# MCU.net
KiCad netlist of a schematic drawn in Altium Designer
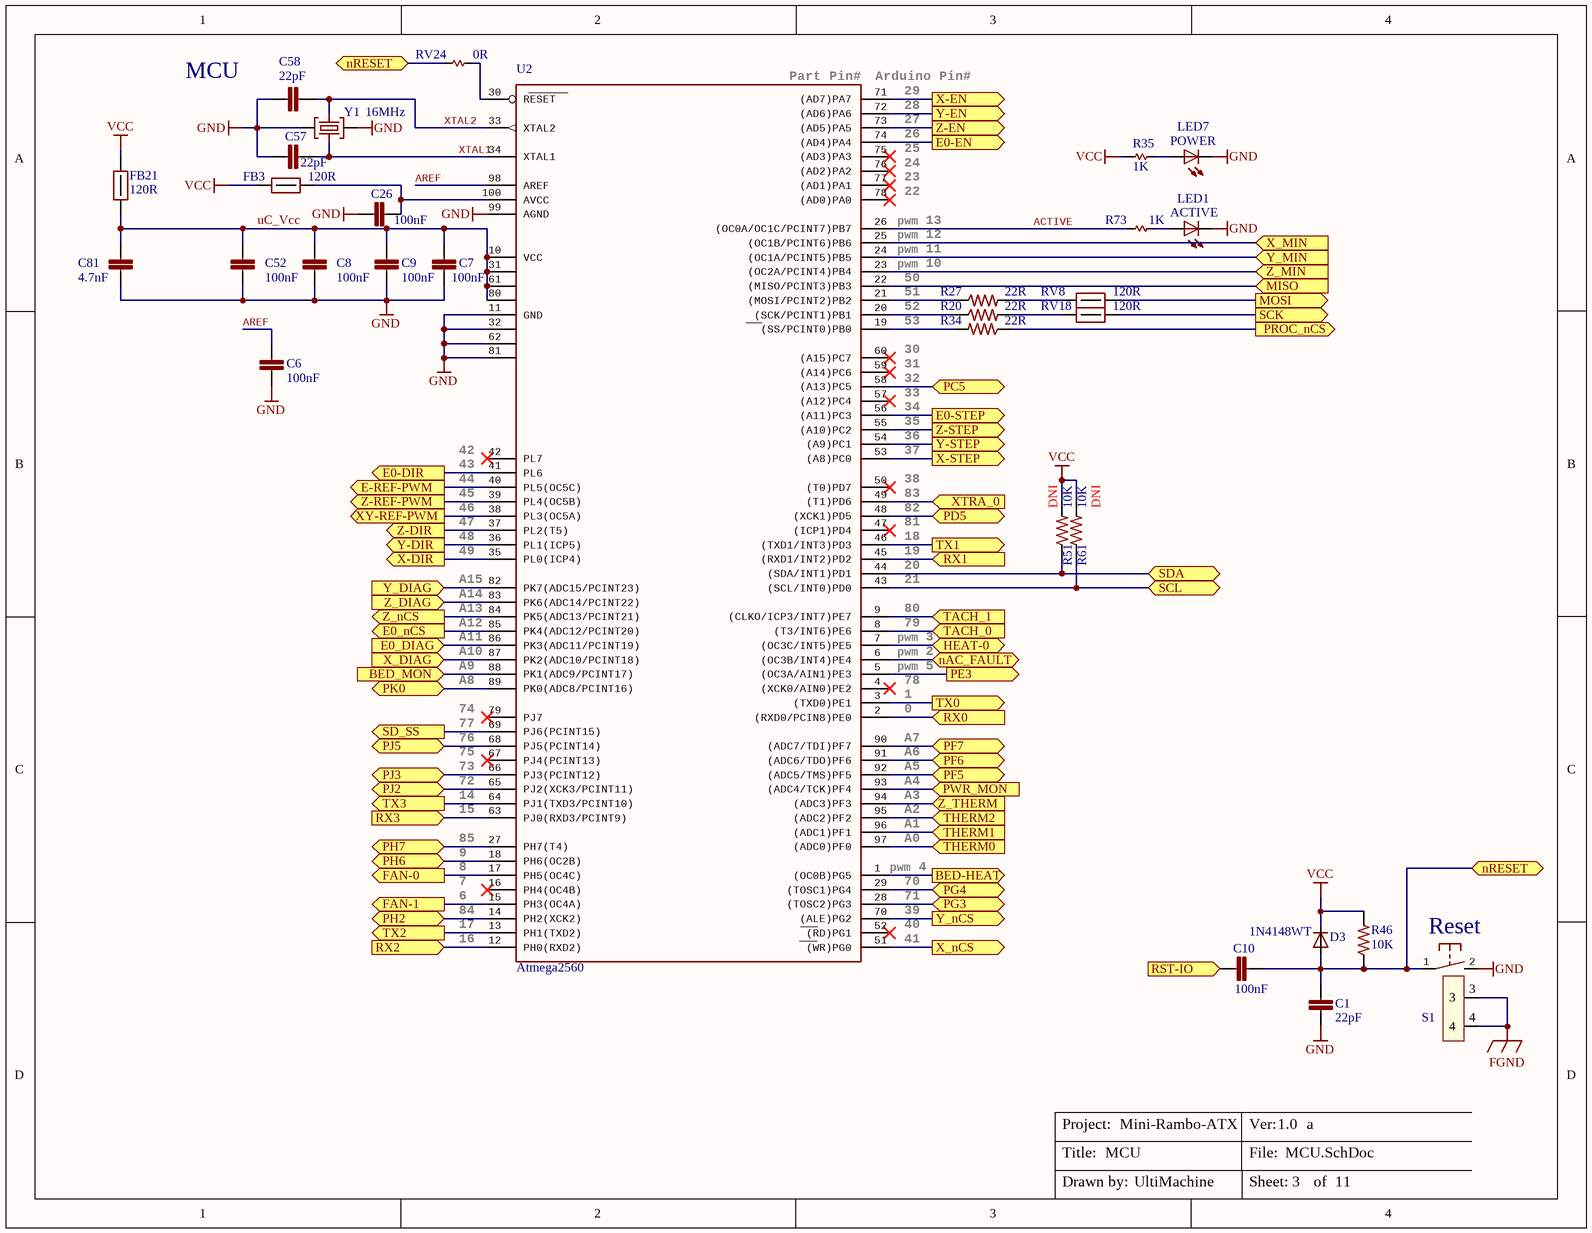
[diagram p0: MCU.SchDoc]

(export (version "E")
  (design (tool "Eeschema 10.0.6"))
  (components
    (comp (ref "C1")
      (value "22pF")
      (footprint "C0402")
      (description "CAP CER 0402 22pF 50V 5% C0G")
      (fields (field (name "MANUFACTURER") "AVX") (field (name "PART") "22pF 50V"))
      (libsource (lib "") (part "04025A220JAT2A_1"))
    )
    (comp (ref "C6")
      (value "100nF")
      (footprint "C0402")
      (description "CAP CER 0402 100nF 16V 10% X7R")
      (fields (field (name "MANUFACTURER") "Murata") (field (name "TOLERANCE") "+/- 10%"))
      (libsource (lib "3Delight") (part "GRM155R71C104KA88D"))
    )
    (comp (ref "C7")
      (value "100nF")
      (footprint "C0402")
      (description "CAP CER 0402 100nF 16V 10% X7R")
      (fields (field (name "MANUFACTURER") "Murata") (field (name "TOLERANCE") "+/- 10%"))
      (libsource (lib "3Delight") (part "GRM155R71C104KA88D"))
    )
    (comp (ref "C8")
      (value "100nF")
      (footprint "C0402")
      (description "CAP CER 0402 100nF 16V 10% X7R")
      (fields (field (name "MANUFACTURER") "Murata") (field (name "TOLERANCE") "+/- 10%"))
      (libsource (lib "3Delight") (part "GRM155R71C104KA88D"))
    )
    (comp (ref "C9")
      (value "100nF")
      (footprint "C0402")
      (description "CAP CER 0402 100nF 16V 10% X7R")
      (fields (field (name "MANUFACTURER") "Murata") (field (name "TOLERANCE") "+/- 10%"))
      (libsource (lib "3Delight") (part "GRM155R71C104KA88D"))
    )
    (comp (ref "C10")
      (value "100nF")
      (footprint "C0402")
      (description "CAP CER 0402 100nF 16V 10% X7R")
      (fields (field (name "MANUFACTURER") "Murata") (field (name "TOLERANCE") "+/- 10%"))
      (libsource (lib "") (part "GRM155R71C104KA88D_2"))
    )
    (comp (ref "C26")
      (value "100nF")
      (footprint "C0402")
      (description "CAP CER 0402 100nF 16V 10% X7R")
      (fields (field (name "MANUFACTURER") "Murata") (field (name "TOLERANCE") "+/- 10%"))
      (libsource (lib "") (part "GRM155R71C104KA88D_1"))
    )
    (comp (ref "C52")
      (value "100nF")
      (footprint "C0402")
      (description "CAP CER 0402 100nF 16V 10% X7R")
      (fields (field (name "MANUFACTURER") "Murata") (field (name "TOLERANCE") "+/- 10%"))
      (libsource (lib "3Delight") (part "GRM155R71C104KA88D"))
    )
    (comp (ref "C57")
      (value "22pF")
      (footprint "C0402")
      (description "CAP CER 0402 22pF 50V 5% C0G")
      (fields (field (name "MANUFACTURER") "AVX") (field (name "PART") "22pF 50V"))
      (libsource (lib "3Delight") (part "04025A220JAT2A"))
    )
    (comp (ref "C58")
      (value "22pF")
      (footprint "C0402")
      (description "CAP CER 0402 22pF 50V 5% C0G")
      (fields (field (name "MANUFACTURER") "AVX") (field (name "PART") "22pF 50V"))
      (libsource (lib "3Delight") (part "04025A220JAT2A"))
    )
    (comp (ref "C81")
      (value "4.7nF")
      (footprint "C0402")
      (description "CAP CER 0402 4.7nF 25V 10% X7R")
      (fields (field (name "MANUFACTURER") "YAGEO") (field (name "TOLERANCE") "+/- 10%"))
      (libsource (lib "3Delight") (part "CC0402KRX7R8BB472"))
    )
    (comp (ref "D3")
      (value "1N4148WT")
      (footprint "SOD523")
      (description "DIODE SOD523")
      (fields (field (name "MANUFACTURER") "Fairchild") (field (name "TOLERANCE") "NA"))
      (libsource (lib "3Delight") (part "1N4148WT"))
    )
    (comp (ref "FB3")
      (value "120R")
      (footprint "FB0603")
      (description "FERRITE BEAD 120 OHM 0603 1LN")
      (fields (field (name "MANUFACTURER") "Samsung") (field (name "PART") "FERRITE 120R 3A 0603"))
      (libsource (lib "3Delight") (part "FERRITE 220R 2.5A 0603"))
    )
    (comp (ref "FB21")
      (value "120R")
      (footprint "FB0603")
      (description "FERRITE BEAD 120 OHM 0603 1LN")
      (fields (field (name "MANUFACTURER") "Samsung") (field (name "PART") "FERRITE 120R 3A 0603"))
      (libsource (lib "Inductors") (part "FERRITE 120R 3A 0603"))
    )
    (comp (ref "LED1")
      (value "YEL")
      (footprint "LED2012120")
      (description "LED 0805 Yellow")
      (fields (field (name "MANUFACTURER") "Dialight") (field (name "TOLERANCE") "NA"))
      (libsource (lib "3Delight") (part "5988140107F"))
    )
    (comp (ref "LED7")
      (value "GRN")
      (footprint "LED2012120")
      (description "LED 0805 Green")
      (fields (field (name "MANUFACTURER") "Dialight") (field (name "TOLERANCE") "NA"))
      (libsource (lib "3Delight") (part "5988170107F"))
    )
    (comp (ref "R20")
      (value "22R")
      (footprint "R0402")
      (description "RES 0402 22r 62.5mW 1%")
      (fields (field (name "MANUFACTURER") "Yageo") (field (name "TOLERANCE") "+/- 1%"))
      (libsource (lib "3Delight") (part "RC0402FR-0722RL"))
    )
    (comp (ref "R27")
      (value "22R")
      (footprint "R0402")
      (description "RES 0402 22r 62.5mW 1%")
      (fields (field (name "MANUFACTURER") "Yageo") (field (name "TOLERANCE") "+/- 1%"))
      (libsource (lib "3Delight") (part "RC0402FR-0722RL"))
    )
    (comp (ref "R34")
      (value "22R")
      (footprint "R0402")
      (description "RES 0402 22r 62.5mW 1%")
      (fields (field (name "MANUFACTURER") "Yageo") (field (name "TOLERANCE") "+/- 1%"))
      (libsource (lib "3Delight") (part "RC0402FR-0722RL"))
    )
    (comp (ref "R35")
      (value "1K")
      (footprint "R0402")
      (description "RES SMD 1K OHM 1% 1/16W 0402")
      (fields (field (name "MANUFACTURER") "Yageo") (field (name "PART") "1k"))
      (libsource (lib "3Delight") (part "RC0402FR-071KL"))
    )
    (comp (ref "R46")
      (value "10K")
      (footprint "R0402")
      (description "RES SMD 10K OHM 1% 1/16W 0402")
      (fields (field (name "MANUFACTURER") "Yageo") (field (name "PART") "10k 1% 0402"))
      (libsource (lib "3Delight") (part "RC0402FR-0710KP"))
    )
    (comp (ref "R51")
      (value "10K")
      (footprint "R0402")
      (description "RES SMD 10K OHM 1% 1/16W 0402")
      (fields
        (field (name "MANUFACTURER") "Yageo")
        (field (name "PART") "10k 1% 0402")
        (field (name "DNI") "DNI")
      )
      (libsource (lib "3Delight") (part "RC0402FR-0710KP"))
    )
    (comp (ref "R61")
      (value "10K")
      (footprint "R0402")
      (description "RES SMD 10K OHM 1% 1/16W 0402")
      (fields
        (field (name "MANUFACTURER") "Yageo")
        (field (name "PART") "10k 1% 0402")
        (field (name "DNI") "DNI")
      )
      (libsource (lib "3Delight") (part "RC0402FR-0710KP"))
    )
    (comp (ref "R73")
      (value "1K")
      (footprint "R0402")
      (description "RES SMD 1K OHM 1% 1/16W 0402")
      (fields (field (name "MANUFACTURER") "Yageo") (field (name "PART") "1k"))
      (libsource (lib "3Delight") (part "RC0402FR-071KL"))
    )
    (comp (ref "RV8")
      (value "120R")
      (footprint "R0402")
      (description "FERRITE BEAD 120 OHM 0402 1LN")
      (fields (field (name "MANUFACTURER") "Taiyo Yuden") (field (name "PART") "FERRITE 120R 1A 0402"))
      (libsource (lib "Inductors") (part "FERRITE 120R 1A 0402"))
    )
    (comp (ref "RV18")
      (value "120R")
      (footprint "R0402")
      (description "FERRITE BEAD 120 OHM 0402 1LN")
      (fields (field (name "MANUFACTURER") "Taiyo Yuden") (field (name "PART") "FERRITE 120R 1A 0402"))
      (libsource (lib "Inductors") (part "FERRITE 120R 1A 0402"))
    )
    (comp (ref "RV24")
      (value "0R")
      (footprint "R0402")
      (description "RES SMD 0.0OHM JUMPER 1/10W 0402")
      (fields (field (name "MANUFACTURER") "Panasonic") (field (name "TOLERANCE") "1%"))
      (libsource (lib "Resistors") (part "0R 0402"))
    )
    (comp (ref "S1")
      (value "1571610-2")
      (footprint "B3F-31XX")
      (description "SWTCH Momentary Washable")
      (fields (field (name "MANUFACTURER") "TE") (field (name "PART") "Tact PB R/A"))
      (libsource (lib "3Delight") (part "1571610-2"))
    )
    (comp (ref "U2")
      (value "Atmega2560")
      (footprint "TSQFP50P1600X1600X120-100L")
      (fields
        (field (name "MANUFACTURER") "Microchip")
        (field (name "PART") "ATMEGA2560")
        (field (name "TOLERANCE") "NA")
      )
      (libsource (lib "ICs-uC") (part "ATMEGA2560AU_SM"))
    )
    (comp (ref "Y1")
      (value "16MHz")
      (footprint "CRYS320250")
      (description "Crystal 16mHz 10ppm 10pF")
      (fields (field (name "MANUFACTURER") "TXC") (field (name "TOLERANCE") "10ppm"))
      (libsource (lib "3Delight") (part "7M-16.000MEEQ-T"))
    )
  )
  (nets
    (net (code "1") (name "/ACTIVE") (class "Default")
      (node (ref "R73") (pin "2") (pinfunction "2_2") (pintype "passive"))
      (node (ref "U2") (pin "26") (pinfunction "(OC0A/OC1C/PCINT7)PB7_26") (pintype "passive"))
    )
    (net (code "2") (name "/AREF") (class "Default")
      (node (ref "C6") (pin "1") (pinfunction "1_1") (pintype "passive"))
      (node (ref "U2") (pin "98") (pinfunction "AREF_98") (pintype "passive"))
    )
    (net (code "3") (name "/BED-HEAT") (class "Default")
      (node (ref "U2") (pin "1") (pinfunction "(OC0B)PG5_1") (pintype "passive"))
    )
    (net (code "4") (name "/BED_MON") (class "Default")
      (node (ref "U2") (pin "88") (pinfunction "PK1(ADC9/PCINT17)_88") (pintype "passive"))
    )
    (net (code "5") (name "/E-REF-PWM") (class "Default")
      (node (ref "U2") (pin "40") (pinfunction "PL5(OC5C)_40") (pintype "passive"))
    )
    (net (code "6") (name "/E0-DIR") (class "Default")
      (node (ref "U2") (pin "41") (pinfunction "PL6_41") (pintype "passive"))
    )
    (net (code "7") (name "/E0-EN") (class "Default")
      (node (ref "U2") (pin "74") (pinfunction "(AD4)PA4_74") (pintype "passive"))
    )
    (net (code "8") (name "/E0-STEP") (class "Default")
      (node (ref "U2") (pin "56") (pinfunction "(A11)PC3_56") (pintype "passive"))
    )
    (net (code "9") (name "/E0_DIAG") (class "Default")
      (node (ref "U2") (pin "86") (pinfunction "PK3(ADC11/PCINT19)_86") (pintype "passive"))
    )
    (net (code "10") (name "/E0_nCS") (class "Default")
      (node (ref "U2") (pin "85") (pinfunction "PK4(ADC12/PCINT20)_85") (pintype "passive"))
    )
    (net (code "11") (name "/FAN-0") (class "Default")
      (node (ref "U2") (pin "17") (pinfunction "PH5(OC4C)_17") (pintype "passive"))
    )
    (net (code "12") (name "/FAN-1") (class "Default")
      (node (ref "U2") (pin "15") (pinfunction "PH3(OC4A)_15") (pintype "passive"))
    )
    (net (code "13") (name "/HEAT-0") (class "Default")
      (node (ref "U2") (pin "7") (pinfunction "(OC3C/INT5)PE5_7") (pintype "passive"))
    )
    (net (code "14") (name "/MISO") (class "Default")
      (node (ref "U2") (pin "22") (pinfunction "(MISO/PCINT3)PB3_22") (pintype "passive"))
    )
    (net (code "15") (name "/MOSI") (class "Default")
      (node (ref "RV8") (pin "2") (pinfunction "2_2") (pintype "passive"))
    )
    (net (code "16") (name "/PC5") (class "Default")
      (node (ref "U2") (pin "58") (pinfunction "(A13)PC5_58") (pintype "passive"))
    )
    (net (code "17") (name "/PD5") (class "Default")
      (node (ref "U2") (pin "48") (pinfunction "(XCK1)PD5_48") (pintype "passive"))
    )
    (net (code "18") (name "/PE3") (class "Default")
      (node (ref "U2") (pin "5") (pinfunction "(OC3A/AIN1)PE3_5") (pintype "passive"))
    )
    (net (code "19") (name "/PF5") (class "Default")
      (node (ref "U2") (pin "92") (pinfunction "(ADC5/TMS)PF5_92") (pintype "passive"))
    )
    (net (code "20") (name "/PF6") (class "Default")
      (node (ref "U2") (pin "91") (pinfunction "(ADC6/TDO)PF6_91") (pintype "passive"))
    )
    (net (code "21") (name "/PF7") (class "Default")
      (node (ref "U2") (pin "90") (pinfunction "(ADC7/TDI)PF7_90") (pintype "passive"))
    )
    (net (code "22") (name "/PG3") (class "Default")
      (node (ref "U2") (pin "28") (pinfunction "(TOSC2)PG3_28") (pintype "passive"))
    )
    (net (code "23") (name "/PG4") (class "Default")
      (node (ref "U2") (pin "29") (pinfunction "(TOSC1)PG4_29") (pintype "passive"))
    )
    (net (code "24") (name "/PH2") (class "Default")
      (node (ref "U2") (pin "14") (pinfunction "PH2(XCK2)_14") (pintype "passive"))
    )
    (net (code "25") (name "/PH6") (class "Default")
      (node (ref "U2") (pin "18") (pinfunction "PH6(OC2B)_18") (pintype "passive"))
    )
    (net (code "26") (name "/PH7") (class "Default")
      (node (ref "U2") (pin "27") (pinfunction "PH7(T4)_27") (pintype "passive"))
    )
    (net (code "27") (name "/PJ2") (class "Default")
      (node (ref "U2") (pin "65") (pinfunction "PJ2(XCK3/PCINT11)_65") (pintype "passive"))
    )
    (net (code "28") (name "/PJ3") (class "Default")
      (node (ref "U2") (pin "66") (pinfunction "PJ3(PCINT12)_66") (pintype "passive"))
    )
    (net (code "29") (name "/PJ5") (class "Default")
      (node (ref "U2") (pin "68") (pinfunction "PJ5(PCINT14)_68") (pintype "passive"))
    )
    (net (code "30") (name "/PK0") (class "Default")
      (node (ref "U2") (pin "89") (pinfunction "PK0(ADC8/PCINT16)_89") (pintype "passive"))
    )
    (net (code "31") (name "/PROC_nCS") (class "Default")
      (node (ref "R34") (pin "1") (pinfunction "1_1") (pintype "passive"))
    )
    (net (code "32") (name "/PWR_MON") (class "Default")
      (node (ref "U2") (pin "93") (pinfunction "(ADC4/TCK)PF4_93") (pintype "passive"))
    )
    (net (code "33") (name "/RST-IO") (class "Default")
      (node (ref "C10") (pin "1") (pinfunction "1_1") (pintype "passive"))
    )
    (net (code "34") (name "/RX0") (class "Default")
      (node (ref "U2") (pin "2") (pinfunction "(RXD0/PCIN8)PE0_2") (pintype "passive"))
    )
    (net (code "35") (name "/RX1") (class "Default")
      (node (ref "U2") (pin "45") (pinfunction "(RXD1/INT2)PD2_45") (pintype "passive"))
    )
    (net (code "36") (name "/RX2") (class "Default")
      (node (ref "U2") (pin "12") (pinfunction "PH0(RXD2)_12") (pintype "passive"))
    )
    (net (code "37") (name "/RX3") (class "Default")
      (node (ref "U2") (pin "63") (pinfunction "PJ0(RXD3/PCINT9)_63") (pintype "passive"))
    )
    (net (code "38") (name "/SCK") (class "Default")
      (node (ref "RV18") (pin "2") (pinfunction "2_2") (pintype "passive"))
    )
    (net (code "39") (name "/SCL") (class "Default")
      (node (ref "R61") (pin "1") (pinfunction "1_1") (pintype "passive"))
      (node (ref "U2") (pin "43") (pinfunction "(SCL/INT0)PD0_43") (pintype "passive"))
    )
    (net (code "40") (name "/SDA") (class "Default")
      (node (ref "R51") (pin "1") (pinfunction "1_1") (pintype "passive"))
      (node (ref "U2") (pin "44") (pinfunction "(SDA/INT1)PD1_44") (pintype "passive"))
    )
    (net (code "41") (name "/SD_SS") (class "Default")
      (node (ref "U2") (pin "69") (pinfunction "PJ6(PCINT15)_69") (pintype "passive"))
    )
    (net (code "42") (name "/TACH_0") (class "Default")
      (node (ref "U2") (pin "8") (pinfunction "(T3/INT6)PE6_8") (pintype "passive"))
    )
    (net (code "43") (name "/TACH_1") (class "Default")
      (node (ref "U2") (pin "9") (pinfunction "(CLKO/ICP3/INT7)PE7_9") (pintype "passive"))
    )
    (net (code "44") (name "/THERM0") (class "Default")
      (node (ref "U2") (pin "97") (pinfunction "(ADC0)PF0_97") (pintype "passive"))
    )
    (net (code "45") (name "/THERM1") (class "Default")
      (node (ref "U2") (pin "96") (pinfunction "(ADC1)PF1_96") (pintype "passive"))
    )
    (net (code "46") (name "/THERM2") (class "Default")
      (node (ref "U2") (pin "95") (pinfunction "(ADC2)PF2_95") (pintype "passive"))
    )
    (net (code "47") (name "/TX0") (class "Default")
      (node (ref "U2") (pin "3") (pinfunction "(TXD0)PE1_3") (pintype "passive"))
    )
    (net (code "48") (name "/TX1") (class "Default")
      (node (ref "U2") (pin "46") (pinfunction "(TXD1/INT3)PD3_46") (pintype "passive"))
    )
    (net (code "49") (name "/TX2") (class "Default")
      (node (ref "U2") (pin "13") (pinfunction "PH1(TXD2)_13") (pintype "passive"))
    )
    (net (code "50") (name "/TX3") (class "Default")
      (node (ref "U2") (pin "64") (pinfunction "PJ1(TXD3/PCINT10)_64") (pintype "passive"))
    )
    (net (code "51") (name "/X-DIR") (class "Default")
      (node (ref "U2") (pin "35") (pinfunction "PL0(ICP4)_35") (pintype "passive"))
    )
    (net (code "52") (name "/X-EN") (class "Default")
      (node (ref "U2") (pin "71") (pinfunction "(AD7)PA7_71") (pintype "passive"))
    )
    (net (code "53") (name "/X-STEP") (class "Default")
      (node (ref "U2") (pin "53") (pinfunction "(A8)PC0_53") (pintype "passive"))
    )
    (net (code "54") (name "/XTAL1") (class "Default")
      (node (ref "C57") (pin "1") (pinfunction "1_1") (pintype "passive"))
      (node (ref "U2") (pin "34") (pinfunction "XTAL1_34") (pintype "passive"))
      (node (ref "Y1") (pin "1") (pinfunction "C1_1") (pintype "passive"))
    )
    (net (code "55") (name "/XTAL2") (class "Default")
      (node (ref "C58") (pin "1") (pinfunction "1_1") (pintype "passive"))
      (node (ref "U2") (pin "33") (pinfunction "XTAL2_33") (pintype "output"))
      (node (ref "Y1") (pin "3") (pinfunction "C2_3") (pintype "passive"))
    )
    (net (code "56") (name "/XTRA_0") (class "Default")
      (node (ref "U2") (pin "49") (pinfunction "(T1)PD6_49") (pintype "passive"))
    )
    (net (code "57") (name "/XY-REF-PWM") (class "Default")
      (node (ref "U2") (pin "38") (pinfunction "PL3(OC5A)_38") (pintype "passive"))
    )
    (net (code "58") (name "/X_DIAG") (class "Default")
      (node (ref "U2") (pin "87") (pinfunction "PK2(ADC10/PCINT18)_87") (pintype "passive"))
    )
    (net (code "59") (name "/X_MIN") (class "Default")
      (node (ref "U2") (pin "25") (pinfunction "(OC1B/PCINT6)PB6_25") (pintype "passive"))
    )
    (net (code "60") (name "/X_nCS") (class "Default")
      (node (ref "U2") (pin "51") (pinfunction "(WR)PG0_51") (pintype "passive"))
    )
    (net (code "61") (name "/Y-DIR") (class "Default")
      (node (ref "U2") (pin "36") (pinfunction "PL1(ICP5)_36") (pintype "passive"))
    )
    (net (code "62") (name "/Y-EN") (class "Default")
      (node (ref "U2") (pin "72") (pinfunction "(AD6)PA6_72") (pintype "passive"))
    )
    (net (code "63") (name "/Y-STEP") (class "Default")
      (node (ref "U2") (pin "54") (pinfunction "(A9)PC1_54") (pintype "passive"))
    )
    (net (code "64") (name "/Y_DIAG") (class "Default")
      (node (ref "U2") (pin "82") (pinfunction "PK7(ADC15/PCINT23)_82") (pintype "passive"))
    )
    (net (code "65") (name "/Y_MIN") (class "Default")
      (node (ref "U2") (pin "24") (pinfunction "(OC1A/PCINT5)PB5_24") (pintype "passive"))
    )
    (net (code "66") (name "/Y_nCS") (class "Default")
      (node (ref "U2") (pin "70") (pinfunction "(ALE)PG2_70") (pintype "passive"))
    )
    (net (code "67") (name "/Z-DIR") (class "Default")
      (node (ref "U2") (pin "37") (pinfunction "PL2(T5)_37") (pintype "passive"))
    )
    (net (code "68") (name "/Z-EN") (class "Default")
      (node (ref "U2") (pin "73") (pinfunction "(AD5)PA5_73") (pintype "passive"))
    )
    (net (code "69") (name "/Z-REF-PWM") (class "Default")
      (node (ref "U2") (pin "39") (pinfunction "PL4(OC5B)_39") (pintype "passive"))
    )
    (net (code "70") (name "/Z-STEP") (class "Default")
      (node (ref "U2") (pin "55") (pinfunction "(A10)PC2_55") (pintype "passive"))
    )
    (net (code "71") (name "/Z_DIAG") (class "Default")
      (node (ref "U2") (pin "83") (pinfunction "PK6(ADC14/PCINT22)_83") (pintype "passive"))
    )
    (net (code "72") (name "/Z_MIN") (class "Default")
      (node (ref "U2") (pin "23") (pinfunction "(OC2A/PCINT4)PB4_23") (pintype "passive"))
    )
    (net (code "73") (name "/Z_THERM") (class "Default")
      (node (ref "U2") (pin "94") (pinfunction "(ADC3)PF3_94") (pintype "passive"))
    )
    (net (code "74") (name "/Z_nCS") (class "Default")
      (node (ref "U2") (pin "84") (pinfunction "PK5(ADC13/PCINT21)_84") (pintype "passive"))
    )
    (net (code "75") (name "/nAC_FAULT") (class "Default")
      (node (ref "U2") (pin "6") (pinfunction "(OC3B/INT4)PE4_6") (pintype "passive"))
    )
    (net (code "76") (name "/nRESET") (class "Default")
      (node (ref "C1") (pin "1") (pinfunction "1_1") (pintype "passive"))
      (node (ref "C10") (pin "2") (pinfunction "2_2") (pintype "passive"))
      (node (ref "D3") (pin "A") (pinfunction "A_A") (pintype "passive"))
      (node (ref "R46") (pin "1") (pinfunction "1_1") (pintype "passive"))
      (node (ref "RV24") (pin "1") (pinfunction "1_1") (pintype "passive"))
      (node (ref "S1") (pin "1") (pinfunction "P_1") (pintype "passive"))
    )
    (net (code "77") (name "/uC_Vcc") (class "Default")
      (node (ref "C52") (pin "1") (pinfunction "1_1") (pintype "passive"))
      (node (ref "C7") (pin "1") (pinfunction "1_1") (pintype "passive"))
      (node (ref "C8") (pin "1") (pinfunction "1_1") (pintype "passive"))
      (node (ref "C81") (pin "1") (pinfunction "1_1") (pintype "passive"))
      (node (ref "C9") (pin "1") (pinfunction "1_1") (pintype "passive"))
      (node (ref "FB21") (pin "2") (pinfunction "2_2") (pintype "passive"))
      (node (ref "U2") (pin "10") (pinfunction "VCC_10") (pintype "power_in"))
      (node (ref "U2") (pin "31") (pinfunction "VCC1_31") (pintype "power_in"))
      (node (ref "U2") (pin "61") (pinfunction "VCC2_61") (pintype "power_in"))
      (node (ref "U2") (pin "80") (pinfunction "VCC3_80") (pintype "power_in"))
    )
    (net (code "78") (name "FGND") (class "Default")
      (node (ref "S1") (pin "3") (pinfunction "3_3") (pintype "power_in"))
      (node (ref "S1") (pin "4") (pinfunction "4_4") (pintype "power_in"))
    )
    (net (code "79") (name "GND") (class "Default")
      (node (ref "C1") (pin "2") (pinfunction "2_2") (pintype "passive"))
      (node (ref "C26") (pin "2") (pinfunction "2_2") (pintype "passive"))
      (node (ref "C52") (pin "2") (pinfunction "2_2") (pintype "passive"))
      (node (ref "C57") (pin "2") (pinfunction "2_2") (pintype "passive"))
      (node (ref "C58") (pin "2") (pinfunction "2_2") (pintype "passive"))
      (node (ref "C6") (pin "2") (pinfunction "2_2") (pintype "passive"))
      (node (ref "C7") (pin "2") (pinfunction "2_2") (pintype "passive"))
      (node (ref "C8") (pin "2") (pinfunction "2_2") (pintype "passive"))
      (node (ref "C81") (pin "2") (pinfunction "2_2") (pintype "passive"))
      (node (ref "C9") (pin "2") (pinfunction "2_2") (pintype "passive"))
      (node (ref "LED1") (pin "C") (pinfunction "C_C") (pintype "passive"))
      (node (ref "LED7") (pin "C") (pinfunction "C_C") (pintype "passive"))
      (node (ref "S1") (pin "2") (pinfunction "S_2") (pintype "passive"))
      (node (ref "U2") (pin "11") (pinfunction "GND_11") (pintype "power_in"))
      (node (ref "U2") (pin "32") (pinfunction "GND1_32") (pintype "power_in"))
      (node (ref "U2") (pin "62") (pinfunction "GND2_62") (pintype "power_in"))
      (node (ref "U2") (pin "81") (pinfunction "GND3_81") (pintype "power_in"))
      (node (ref "U2") (pin "99") (pinfunction "AGND_99") (pintype "power_in"))
      (node (ref "Y1") (pin "2") (pinfunction "GND_2") (pintype "passive"))
      (node (ref "Y1") (pin "4") (pinfunction "GND_4") (pintype "passive"))
    )
    (net (code "80") (name "Net-(LED1-PadA)") (class "Default")
      (node (ref "LED1") (pin "A") (pinfunction "A_A") (pintype "passive"))
      (node (ref "R73") (pin "1") (pinfunction "1_1") (pintype "passive"))
    )
    (net (code "81") (name "Net-(LED7-PadA)") (class "Default")
      (node (ref "LED7") (pin "A") (pinfunction "A_A") (pintype "passive"))
      (node (ref "R35") (pin "1") (pinfunction "1_1") (pintype "passive"))
    )
    (net (code "82") (name "Net-(R20-Pad2)") (class "Default")
      (node (ref "R20") (pin "2") (pinfunction "2_2") (pintype "passive"))
      (node (ref "RV18") (pin "1") (pinfunction "1_1") (pintype "passive"))
    )
    (net (code "83") (name "Net-(R27-Pad2)") (class "Default")
      (node (ref "R27") (pin "2") (pinfunction "2_2") (pintype "passive"))
      (node (ref "RV8") (pin "1") (pinfunction "1_1") (pintype "passive"))
    )
    (net (code "84") (name "Net-(U2-(MOSI{slash}PCINT2)PB2)") (class "Default")
      (node (ref "R27") (pin "1") (pinfunction "1_1") (pintype "passive"))
      (node (ref "U2") (pin "21") (pinfunction "(MOSI/PCINT2)PB2_21") (pintype "passive"))
    )
    (net (code "85") (name "Net-(U2-(SCK{slash}PCINT1)PB1)") (class "Default")
      (node (ref "R20") (pin "1") (pinfunction "1_1") (pintype "passive"))
      (node (ref "U2") (pin "20") (pinfunction "(SCK/PCINT1)PB1_20") (pintype "passive"))
    )
    (net (code "86") (name "Net-(U2-(SS{slash}PCINT0)PB0)") (class "Default")
      (node (ref "R34") (pin "2") (pinfunction "2_2") (pintype "passive"))
      (node (ref "U2") (pin "19") (pinfunction "(SS/PCINT0)PB0_19") (pintype "passive"))
    )
    (net (code "87") (name "Net-(U2-AVCC)") (class "Default")
      (node (ref "C26") (pin "1") (pinfunction "1_1") (pintype "passive"))
      (node (ref "FB3") (pin "2") (pinfunction "2_2") (pintype "passive"))
      (node (ref "U2") (pin "100") (pinfunction "AVCC_100") (pintype "power_in"))
    )
    (net (code "88") (name "Net-(U2-RESET)") (class "Default")
      (node (ref "RV24") (pin "2") (pinfunction "2_2") (pintype "passive"))
      (node (ref "U2") (pin "30") (pinfunction "RESET_30") (pintype "passive"))
    )
    (net (code "89") (name "VCC") (class "Default")
      (node (ref "D3") (pin "C") (pinfunction "C_C") (pintype "passive"))
      (node (ref "FB21") (pin "1") (pinfunction "1_1") (pintype "passive"))
      (node (ref "FB3") (pin "1") (pinfunction "1_1") (pintype "passive"))
      (node (ref "R35") (pin "2") (pinfunction "2_2") (pintype "passive"))
      (node (ref "R46") (pin "2") (pinfunction "2_2") (pintype "passive"))
      (node (ref "R51") (pin "2") (pinfunction "2_2") (pintype "passive"))
      (node (ref "R61") (pin "2") (pinfunction "2_2") (pintype "passive"))
    )
    (net (code "90") (name "unconnected-(U2-(A12)PC4-Pad57)") (class "Default")
      (node (ref "U2") (pin "57") (pinfunction "(A12)PC4_57") (pintype "passive+no_connect"))
    )
    (net (code "91") (name "unconnected-(U2-(A14)PC6-Pad59)") (class "Default")
      (node (ref "U2") (pin "59") (pinfunction "(A14)PC6_59") (pintype "passive+no_connect"))
    )
    (net (code "92") (name "unconnected-(U2-(A15)PC7-Pad60)") (class "Default")
      (node (ref "U2") (pin "60") (pinfunction "(A15)PC7_60") (pintype "passive+no_connect"))
    )
    (net (code "93") (name "unconnected-(U2-(AD0)PA0-Pad78)") (class "Default")
      (node (ref "U2") (pin "78") (pinfunction "(AD0)PA0_78") (pintype "passive+no_connect"))
    )
    (net (code "94") (name "unconnected-(U2-(AD1)PA1-Pad77)") (class "Default")
      (node (ref "U2") (pin "77") (pinfunction "(AD1)PA1_77") (pintype "passive+no_connect"))
    )
    (net (code "95") (name "unconnected-(U2-(AD2)PA2-Pad76)") (class "Default")
      (node (ref "U2") (pin "76") (pinfunction "(AD2)PA2_76") (pintype "passive+no_connect"))
    )
    (net (code "96") (name "unconnected-(U2-(AD3)PA3-Pad75)") (class "Default")
      (node (ref "U2") (pin "75") (pinfunction "(AD3)PA3_75") (pintype "passive+no_connect"))
    )
    (net (code "97") (name "unconnected-(U2-(ICP1)PD4-Pad47)") (class "Default")
      (node (ref "U2") (pin "47") (pinfunction "(ICP1)PD4_47") (pintype "passive+no_connect"))
    )
    (net (code "98") (name "unconnected-(U2-(RD)PG1-Pad52)") (class "Default")
      (node (ref "U2") (pin "52") (pinfunction "(RD)PG1_52") (pintype "passive+no_connect"))
    )
    (net (code "99") (name "unconnected-(U2-(T0)PD7-Pad50)") (class "Default")
      (node (ref "U2") (pin "50") (pinfunction "(T0)PD7_50") (pintype "passive+no_connect"))
    )
    (net (code "100") (name "unconnected-(U2-(XCK0{slash}AIN0)PE2-Pad4)") (class "Default")
      (node (ref "U2") (pin "4") (pinfunction "(XCK0/AIN0)PE2_4") (pintype "passive+no_connect"))
    )
    (net (code "101") (name "unconnected-(U2-PH4(OC4B)-Pad16)") (class "Default")
      (node (ref "U2") (pin "16") (pinfunction "PH4(OC4B)_16") (pintype "passive+no_connect"))
    )
    (net (code "102") (name "unconnected-(U2-PJ4(PCINT13)-Pad67)") (class "Default")
      (node (ref "U2") (pin "67") (pinfunction "PJ4(PCINT13)_67") (pintype "passive+no_connect"))
    )
    (net (code "103") (name "unconnected-(U2-PJ7-Pad79)") (class "Default")
      (node (ref "U2") (pin "79") (pinfunction "PJ7_79") (pintype "passive+no_connect"))
    )
    (net (code "104") (name "unconnected-(U2-PL7-Pad42)") (class "Default")
      (node (ref "U2") (pin "42") (pinfunction "PL7_42") (pintype "passive+no_connect"))
    )
  )
)
